# RelayBoard.net
KiCad netlist of a schematic drawn in Altium Designer
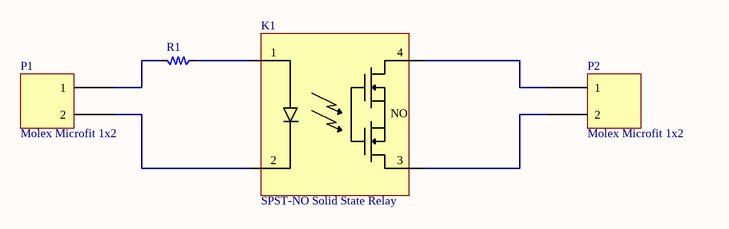
[diagram p0: RelayBoard.SchDoc]

(export (version "E")
  (design (tool "Eeschema 10.0.6"))
  (components
    (comp (ref "K1")
      (value "SPST-NO Solid State Relay")
      (footprint "SPST-NO Solid State Relay - IXYS")
      (libsource (lib "SPST-NO Solid State Relay") (part "SPST-NO Solid State Relay"))
    )
    (comp (ref "P1")
      (value "Molex Microfit 1x2")
      (footprint "PCB_MLX_MICROFIT_1X2")
      (libsource (lib "Molex Microfit 3.0 1x2") (part "SCH_MLX_1X2"))
    )
    (comp (ref "P2")
      (value "Molex Microfit 1x2")
      (footprint "PCB_MLX_MICROFIT_1X2")
      (libsource (lib "") (part "SCH_MLX_1X2_1"))
    )
    (comp (ref "R1")
      (value "SCH_GENERIC_RESISTOR_0603")
      (footprint "PCB_GENERIC_SMD_0603")
      (description "Generic SMD resistor 0603")
      (libsource (lib "Generic 0603 Resistor") (part "SCH_GENERIC_RESISTOR_0603"))
    )
  )
  (nets
    (net (code "1") (name "Net-(K1-Control_+)") (class "Default")
      (node (ref "K1") (pin "1") (pinfunction "Control_+_1") (pintype "passive"))
      (node (ref "R1") (pin "1") (pinfunction "1_1") (pintype "passive"))
    )
    (net (code "2") (name "Net-(K1-Control_-)") (class "Default")
      (node (ref "K1") (pin "2") (pinfunction "Control_-_2") (pintype "passive"))
      (node (ref "P1") (pin "2") (pinfunction "2_2") (pintype "passive"))
    )
    (net (code "3") (name "Net-(K1-Load-Pad3)") (class "Default")
      (node (ref "K1") (pin "3") (pinfunction "Load_3") (pintype "passive"))
      (node (ref "P2") (pin "2") (pinfunction "2_2") (pintype "passive"))
    )
    (net (code "4") (name "Net-(K1-Load-Pad4)") (class "Default")
      (node (ref "K1") (pin "4") (pinfunction "Load_4") (pintype "passive"))
      (node (ref "P2") (pin "1") (pinfunction "1_1") (pintype "passive"))
    )
    (net (code "5") (name "Net-(P1-Pad1)") (class "Default")
      (node (ref "P1") (pin "1") (pinfunction "1_1") (pintype "passive"))
      (node (ref "R1") (pin "2") (pinfunction "2_2") (pintype "passive"))
    )
  )
)
